# tractor_v2.net
KiCad netlist of a schematic drawn in EAGLE
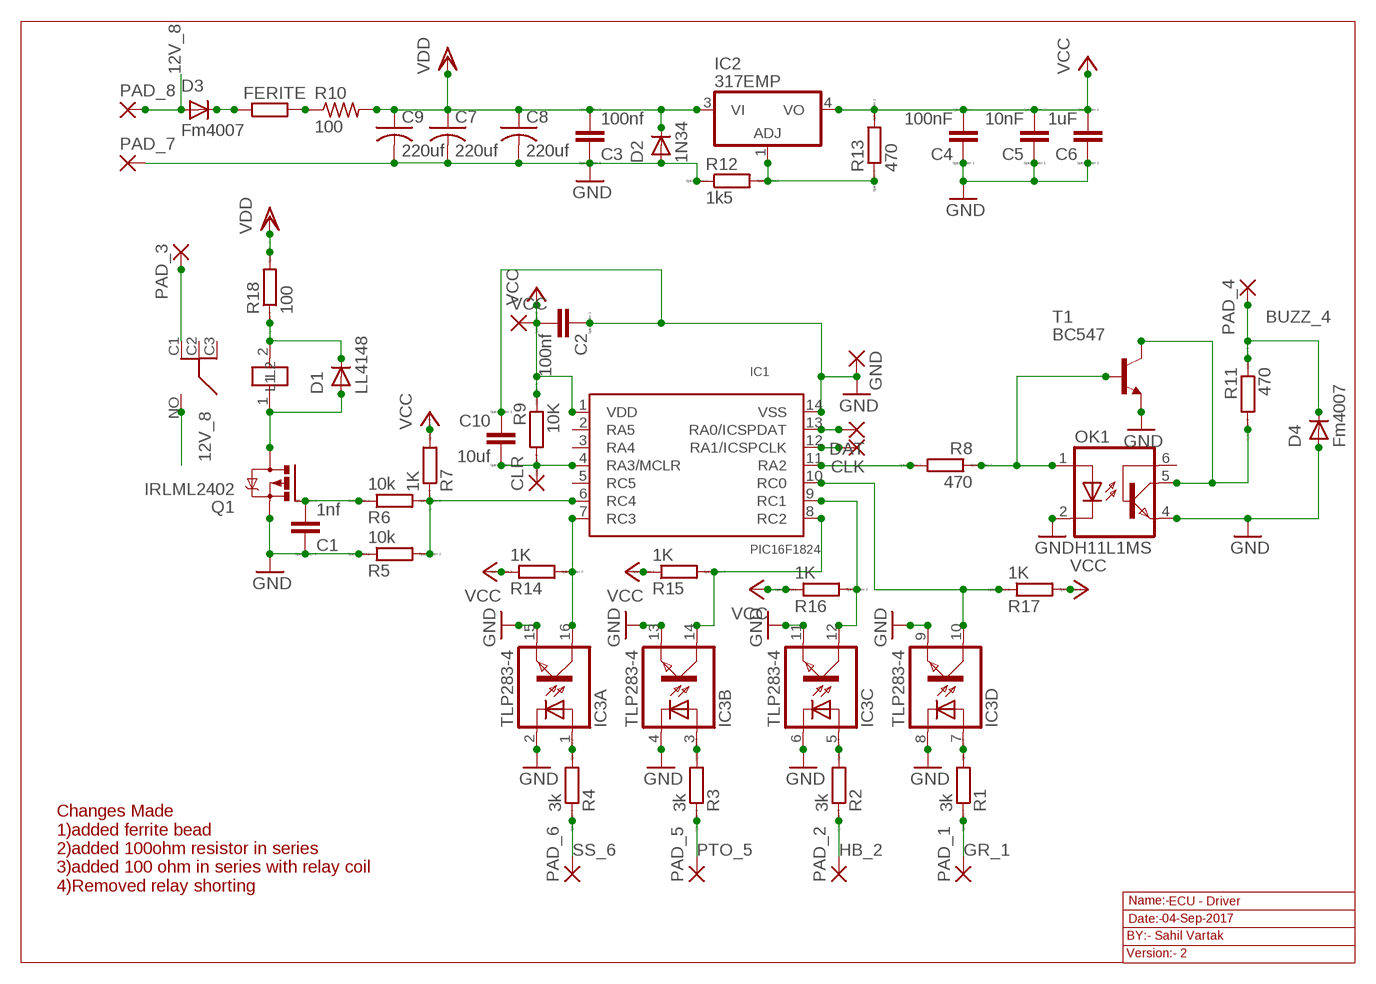
[diagram p0: schematic, sheet 1]

(export (version "E")
  (design (tool "Eeschema 10.0.6"))
  (components
    (comp (ref "C1")
      (value "1nf")
      (footprint "eagle-import:C0603")
      (libsource (lib "eagle-import") (part "CC0603"))
    )
    (comp (ref "C2")
      (value "100nf")
      (footprint "eagle-import:C0603")
      (libsource (lib "eagle-import") (part "CC0603"))
    )
    (comp (ref "C3")
      (value "100nf")
      (footprint "eagle-import:C0603")
      (libsource (lib "eagle-import") (part "CC0603"))
    )
    (comp (ref "C4")
      (value "100nF")
      (footprint "eagle-import:C0603")
      (libsource (lib "eagle-import") (part "CC0603"))
    )
    (comp (ref "C5")
      (value "10nF")
      (footprint "eagle-import:C0603")
      (libsource (lib "eagle-import") (part "CC0603"))
    )
    (comp (ref "C6")
      (value "1uF")
      (footprint "eagle-import:C0603")
      (libsource (lib "eagle-import") (part "CC0603"))
    )
    (comp (ref "C7")
      (value "220uf")
      (footprint "eagle-import:C025-025X050")
      (libsource (lib "eagle-import") (part "C-US025-025X050"))
    )
    (comp (ref "C8")
      (value "220uf")
      (footprint "eagle-import:C025-025X050")
      (libsource (lib "eagle-import") (part "C-US025-025X050"))
    )
    (comp (ref "C9")
      (value "220uf")
      (footprint "eagle-import:C025-025X050")
      (libsource (lib "eagle-import") (part "C-US025-025X050"))
    )
    (comp (ref "C10")
      (value "10uf")
      (footprint "eagle-import:C0603")
      (libsource (lib "eagle-import") (part "CC0603"))
    )
    (comp (ref "CLK")
      (value "1,6/0,8")
      (footprint "eagle-import:1,6_0,8")
      (libsource (lib "eagle-import") (part "1,6/0,8"))
    )
    (comp (ref "CLR")
      (value "1,6/0,8")
      (footprint "eagle-import:1,6_0,8")
      (libsource (lib "eagle-import") (part "1,6/0,8"))
    )
    (comp (ref "D1")
      (value "LL4148")
      (footprint "eagle-import:SMA-DO214AC")
      (libsource (lib "eagle-import") (part "GF1"))
    )
    (comp (ref "D2")
      (value "1N34")
      (footprint "eagle-import:SMA-DO214AC")
      (libsource (lib "eagle-import") (part "GF1"))
    )
    (comp (ref "D3")
      (value "Fm4007")
      (footprint "eagle-import:SMA-DO214AC")
      (libsource (lib "eagle-import") (part "GF1"))
    )
    (comp (ref "D4")
      (value "Fm4007")
      (footprint "eagle-import:SMA-DO214AC")
      (libsource (lib "eagle-import") (part "GF1"))
    )
    (comp (ref "DAT")
      (value "1,6/0,8")
      (footprint "eagle-import:1,6_0,8")
      (libsource (lib "eagle-import") (part "1,6/0,8"))
    )
    (comp (ref "FERITE")
      (value "R-EU_R0603")
      (footprint "eagle-import:R0603")
      (libsource (lib "eagle-import") (part "R-EU_R0603"))
    )
    (comp (ref "GND")
      (value "1,6/0,8")
      (footprint "eagle-import:1,6_0,8")
      (libsource (lib "eagle-import") (part "1,6/0,8"))
    )
    (comp (ref "IC1")
      (value "PIC16F1824")
      (footprint "eagle-import:SO-14")
      (libsource (lib "eagle-import") (part "PIC16F1824"))
    )
    (comp (ref "IC2")
      (value "317EMP")
      (footprint "eagle-import:SOT223")
      (libsource (lib "eagle-import") (part "317EMP"))
    )
    (comp (ref "IC3")
      (value "TLP283-4")
      (footprint "eagle-import:MINI-FLAT-16")
      (libsource (lib "eagle-import") (part "TLP283-4"))
    )
    (comp (ref "K2")
      (value "RL703")
      (footprint "eagle-import:RL703")
      (libsource (lib "eagle-import") (part "RL703"))
    )
    (comp (ref "OK1")
      (value "H11L1MS")
      (footprint "eagle-import:DIL6-SMD")
      (libsource (lib "eagle-import") (part "H11LMS1"))
    )
    (comp (ref "PAD_1")
      (value "2,54/1,1")
      (footprint "eagle-import:2,54_1,1")
      (libsource (lib "eagle-import") (part "2,54/1,1"))
    )
    (comp (ref "PAD_2")
      (value "2,54/1,1")
      (footprint "eagle-import:2,54_1,1")
      (libsource (lib "eagle-import") (part "2,54/1,1"))
    )
    (comp (ref "PAD_3")
      (value "2,54/1,1")
      (footprint "eagle-import:2,54_1,1")
      (libsource (lib "eagle-import") (part "2,54/1,1"))
    )
    (comp (ref "PAD_4")
      (value "2,54/1,1")
      (footprint "eagle-import:2,54_1,1")
      (libsource (lib "eagle-import") (part "2,54/1,1"))
    )
    (comp (ref "PAD_5")
      (value "2,54/1,1")
      (footprint "eagle-import:2,54_1,1")
      (libsource (lib "eagle-import") (part "2,54/1,1"))
    )
    (comp (ref "PAD_6")
      (value "2,54/1,1")
      (footprint "eagle-import:2,54_1,1")
      (libsource (lib "eagle-import") (part "2,54/1,1"))
    )
    (comp (ref "PAD_7")
      (value "2,54/1,1")
      (footprint "eagle-import:2,54_1,1")
      (libsource (lib "eagle-import") (part "2,54/1,1"))
    )
    (comp (ref "PAD_8")
      (value "2,54/1,1")
      (footprint "eagle-import:2,54_1,1")
      (libsource (lib "eagle-import") (part "2,54/1,1"))
    )
    (comp (ref "Q1")
      (value "IRLML2402")
      (footprint "eagle-import:MICRO3")
      (libsource (lib "eagle-import") (part "IRLML5203"))
    )
    (comp (ref "R1")
      (value "3k")
      (footprint "eagle-import:R0603")
      (libsource (lib "eagle-import") (part "RR0603"))
    )
    (comp (ref "R2")
      (value "3k")
      (footprint "eagle-import:R0603")
      (libsource (lib "eagle-import") (part "RR0603"))
    )
    (comp (ref "R3")
      (value "3k")
      (footprint "eagle-import:R0603")
      (libsource (lib "eagle-import") (part "RR0603"))
    )
    (comp (ref "R4")
      (value "3k")
      (footprint "eagle-import:R0603")
      (libsource (lib "eagle-import") (part "RR0603"))
    )
    (comp (ref "R5")
      (value "10k")
      (footprint "eagle-import:R0603")
      (libsource (lib "eagle-import") (part "RR0603"))
    )
    (comp (ref "R6")
      (value "10k")
      (footprint "eagle-import:R0603")
      (libsource (lib "eagle-import") (part "RR0603"))
    )
    (comp (ref "R7")
      (value "1K")
      (footprint "eagle-import:R0603")
      (libsource (lib "eagle-import") (part "RR0603"))
    )
    (comp (ref "R8")
      (value "470")
      (footprint "eagle-import:R0603")
      (libsource (lib "eagle-import") (part "RR0603"))
    )
    (comp (ref "R9")
      (value "10K")
      (footprint "eagle-import:R0603")
      (libsource (lib "eagle-import") (part "RR0603"))
    )
    (comp (ref "R10")
      (value "100")
      (footprint "eagle-import:WSC2515")
      (libsource (lib "eagle-import") (part "R-US_WSC2515"))
    )
    (comp (ref "R11")
      (value "470")
      (footprint "eagle-import:R0603")
      (libsource (lib "eagle-import") (part "RR0603"))
    )
    (comp (ref "R12")
      (value "1k5")
      (footprint "eagle-import:R0603")
      (libsource (lib "eagle-import") (part "RR0603"))
    )
    (comp (ref "R13")
      (value "470")
      (footprint "eagle-import:R0603")
      (libsource (lib "eagle-import") (part "RR0603"))
    )
    (comp (ref "R14")
      (value "1K")
      (footprint "eagle-import:R0603")
      (libsource (lib "eagle-import") (part "RR0603"))
    )
    (comp (ref "R15")
      (value "1K")
      (footprint "eagle-import:R0603")
      (libsource (lib "eagle-import") (part "RR0603"))
    )
    (comp (ref "R16")
      (value "1K")
      (footprint "eagle-import:R0603")
      (libsource (lib "eagle-import") (part "RR0603"))
    )
    (comp (ref "R17")
      (value "1K")
      (footprint "eagle-import:R0603")
      (libsource (lib "eagle-import") (part "RR0603"))
    )
    (comp (ref "R18")
      (value "100")
      (footprint "eagle-import:R0603")
      (libsource (lib "eagle-import") (part "RR0603"))
    )
    (comp (ref "T1")
      (value "BC547")
      (footprint "eagle-import:TO92")
      (libsource (lib "eagle-import") (part "BC547"))
    )
    (comp (ref "VCC")
      (value "1,6/0,8")
      (footprint "eagle-import:1,6_0,8")
      (libsource (lib "eagle-import") (part "1,6/0,8"))
    )
  )
  (nets
    (net (code "1") (name "/12V_8") (class "Default")
      (node (ref "D3") (pin "A") (pinfunction "A_A") (pintype "passive"))
      (node (ref "K2") (pin "NO") (pinfunction "NO_NO") (pintype "bidirectional"))
      (node (ref "PAD_8") (pin "1") (pinfunction "P_1") (pintype "passive"))
    )
    (net (code "2") (name "/BUZZ_4") (class "Default")
      (node (ref "D4") (pin "K") (pinfunction "C_K") (pintype "passive"))
      (node (ref "PAD_4") (pin "1") (pinfunction "P_1") (pintype "passive"))
      (node (ref "R11") (pin "1") (pinfunction "1_1") (pintype "passive"))
    )
    (net (code "3") (name "/GR_1") (class "Default")
      (node (ref "PAD_1") (pin "1") (pinfunction "P_1") (pintype "passive"))
      (node (ref "R1") (pin "1") (pinfunction "1_1") (pintype "passive"))
    )
    (net (code "4") (name "/HB_2") (class "Default")
      (node (ref "PAD_2") (pin "1") (pinfunction "P_1") (pintype "passive"))
      (node (ref "R2") (pin "1") (pinfunction "1_1") (pintype "passive"))
    )
    (net (code "5") (name "/PTO_5") (class "Default")
      (node (ref "PAD_5") (pin "1") (pinfunction "P_1") (pintype "passive"))
      (node (ref "R3") (pin "1") (pinfunction "1_1") (pintype "passive"))
    )
    (net (code "6") (name "/SS_6") (class "Default")
      (node (ref "PAD_6") (pin "1") (pinfunction "P_1") (pintype "passive"))
      (node (ref "R4") (pin "1") (pinfunction "1_1") (pintype "passive"))
    )
    (net (code "7") (name "GND") (class "Default")
      (node (ref "C1") (pin "1") (pinfunction "1_1") (pintype "passive"))
      (node (ref "C10") (pin "1") (pinfunction "1_1") (pintype "passive"))
      (node (ref "C2") (pin "1") (pinfunction "1_1") (pintype "passive"))
      (node (ref "C3") (pin "1") (pinfunction "1_1") (pintype "passive"))
      (node (ref "C4") (pin "1") (pinfunction "1_1") (pintype "passive"))
      (node (ref "C5") (pin "1") (pinfunction "1_1") (pintype "passive"))
      (node (ref "C6") (pin "1") (pinfunction "1_1") (pintype "passive"))
      (node (ref "C7") (pin "2") (pinfunction "2_2") (pintype "passive"))
      (node (ref "C8") (pin "2") (pinfunction "2_2") (pintype "passive"))
      (node (ref "C9") (pin "2") (pinfunction "2_2") (pintype "passive"))
      (node (ref "D2") (pin "A") (pinfunction "A_A") (pintype "passive"))
      (node (ref "D4") (pin "A") (pinfunction "A_A") (pintype "passive"))
      (node (ref "GND") (pin "1") (pinfunction "P_1") (pintype "passive"))
      (node (ref "IC1") (pin "14") (pinfunction "VSS_14") (pintype "bidirectional"))
      (node (ref "IC3") (pin "11") (pinfunction "EMIT_11") (pintype "passive"))
      (node (ref "IC3") (pin "13") (pinfunction "EMIT_13") (pintype "passive"))
      (node (ref "IC3") (pin "15") (pinfunction "EMIT_15") (pintype "passive"))
      (node (ref "IC3") (pin "2") (pinfunction "C_2") (pintype "passive"))
      (node (ref "IC3") (pin "4") (pinfunction "C_4") (pintype "passive"))
      (node (ref "IC3") (pin "6") (pinfunction "C_6") (pintype "passive"))
      (node (ref "IC3") (pin "8") (pinfunction "C_8") (pintype "passive"))
      (node (ref "IC3") (pin "9") (pinfunction "EMIT_9") (pintype "passive"))
      (node (ref "OK1") (pin "2") (pinfunction "C_2") (pintype "passive"))
      (node (ref "OK1") (pin "4") (pinfunction "EMI_4") (pintype "passive"))
      (node (ref "PAD_7") (pin "1") (pinfunction "P_1") (pintype "passive"))
      (node (ref "Q1") (pin "2") (pinfunction "S_2") (pintype "passive"))
      (node (ref "R12") (pin "1") (pinfunction "1_1") (pintype "passive"))
      (node (ref "R5") (pin "1") (pinfunction "1_1") (pintype "passive"))
      (node (ref "T1") (pin "1") (pinfunction "E_1") (pintype "passive"))
    )
    (net (code "8") (name "Net-(CLK-P)") (class "Default")
      (node (ref "CLK") (pin "1") (pinfunction "P_1") (pintype "passive"))
      (node (ref "IC1") (pin "12") (pinfunction "RA1/ICSPCLK_12") (pintype "bidirectional"))
    )
    (net (code "9") (name "Net-(CLR-P)") (class "Default")
      (node (ref "C10") (pin "2") (pinfunction "2_2") (pintype "passive"))
      (node (ref "CLR") (pin "1") (pinfunction "P_1") (pintype "passive"))
      (node (ref "IC1") (pin "4") (pinfunction "RA3/MCLR_4") (pintype "bidirectional"))
      (node (ref "R9") (pin "2") (pinfunction "2_2") (pintype "passive"))
    )
    (net (code "10") (name "Net-(D1-C)") (class "Default")
      (node (ref "D1") (pin "K") (pinfunction "C_K") (pintype "passive"))
      (node (ref "K2") (pin "2") (pinfunction "L1_2") (pintype "bidirectional"))
      (node (ref "R18") (pin "1") (pinfunction "1_1") (pintype "passive"))
    )
    (net (code "11") (name "Net-(D3-C)") (class "Default")
      (node (ref "D3") (pin "K") (pinfunction "C_K") (pintype "passive"))
      (node (ref "FERITE") (pin "1") (pinfunction "1_1") (pintype "passive"))
    )
    (net (code "12") (name "Net-(DAT-P)") (class "Default")
      (node (ref "DAT") (pin "1") (pinfunction "P_1") (pintype "passive"))
      (node (ref "IC1") (pin "13") (pinfunction "RA0/ICSPDAT_13") (pintype "bidirectional"))
    )
    (net (code "13") (name "Net-(FERITE-Pad2)") (class "Default")
      (node (ref "FERITE") (pin "2") (pinfunction "2_2") (pintype "passive"))
      (node (ref "R10") (pin "1") (pinfunction "1_1") (pintype "passive"))
    )
    (net (code "14") (name "Net-(IC1-RA2)") (class "Default")
      (node (ref "IC1") (pin "11") (pinfunction "RA2_11") (pintype "bidirectional"))
      (node (ref "R8") (pin "2") (pinfunction "2_2") (pintype "passive"))
    )
    (net (code "15") (name "Net-(IC1-RC0)") (class "Default")
      (node (ref "IC1") (pin "10") (pinfunction "RC0_10") (pintype "bidirectional"))
      (node (ref "IC3") (pin "10") (pinfunction "COL_10") (pintype "passive"))
      (node (ref "R17") (pin "1") (pinfunction "1_1") (pintype "passive"))
    )
    (net (code "16") (name "Net-(IC1-RC1)") (class "Default")
      (node (ref "IC1") (pin "9") (pinfunction "RC1_9") (pintype "bidirectional"))
      (node (ref "IC3") (pin "12") (pinfunction "COL_12") (pintype "passive"))
      (node (ref "R16") (pin "2") (pinfunction "2_2") (pintype "passive"))
    )
    (net (code "17") (name "Net-(IC1-RC2)") (class "Default")
      (node (ref "IC1") (pin "8") (pinfunction "RC2_8") (pintype "bidirectional"))
      (node (ref "IC3") (pin "14") (pinfunction "COL_14") (pintype "passive"))
      (node (ref "R15") (pin "2") (pinfunction "2_2") (pintype "passive"))
    )
    (net (code "18") (name "Net-(IC1-RC3)") (class "Default")
      (node (ref "IC1") (pin "7") (pinfunction "RC3_7") (pintype "bidirectional"))
      (node (ref "IC3") (pin "16") (pinfunction "COL_16") (pintype "passive"))
      (node (ref "R14") (pin "2") (pinfunction "2_2") (pintype "passive"))
    )
    (net (code "19") (name "Net-(IC1-RC4)") (class "Default")
      (node (ref "IC1") (pin "6") (pinfunction "RC4_6") (pintype "bidirectional"))
      (node (ref "R5") (pin "2") (pinfunction "2_2") (pintype "passive"))
      (node (ref "R6") (pin "2") (pinfunction "2_2") (pintype "passive"))
      (node (ref "R7") (pin "1") (pinfunction "1_1") (pintype "passive"))
    )
    (net (code "20") (name "Net-(IC2-ADJ)") (class "Default")
      (node (ref "IC2") (pin "1") (pinfunction "ADJ_1") (pintype "input"))
      (node (ref "R12") (pin "2") (pinfunction "2_2") (pintype "passive"))
      (node (ref "R13") (pin "1") (pinfunction "1_1") (pintype "passive"))
    )
    (net (code "21") (name "Net-(IC3A-A)") (class "Default")
      (node (ref "IC3") (pin "1") (pinfunction "A_1") (pintype "passive"))
      (node (ref "R4") (pin "2") (pinfunction "2_2") (pintype "passive"))
    )
    (net (code "22") (name "Net-(IC3B-A)") (class "Default")
      (node (ref "IC3") (pin "3") (pinfunction "A_3") (pintype "passive"))
      (node (ref "R3") (pin "2") (pinfunction "2_2") (pintype "passive"))
    )
    (net (code "23") (name "Net-(IC3C-A)") (class "Default")
      (node (ref "IC3") (pin "5") (pinfunction "A_5") (pintype "passive"))
      (node (ref "R2") (pin "2") (pinfunction "2_2") (pintype "passive"))
    )
    (net (code "24") (name "Net-(IC3D-A)") (class "Default")
      (node (ref "IC3") (pin "7") (pinfunction "A_7") (pintype "passive"))
      (node (ref "R1") (pin "2") (pinfunction "2_2") (pintype "passive"))
    )
    (net (code "25") (name "Net-(K2-L2)") (class "Default")
      (node (ref "D1") (pin "A") (pinfunction "A_A") (pintype "passive"))
      (node (ref "K2") (pin "1") (pinfunction "L2_1") (pintype "bidirectional"))
      (node (ref "Q1") (pin "3") (pinfunction "D_3") (pintype "passive"))
    )
    (net (code "26") (name "Net-(OK1-A)") (class "Default")
      (node (ref "OK1") (pin "1") (pinfunction "A_1") (pintype "passive"))
      (node (ref "R8") (pin "1") (pinfunction "1_1") (pintype "passive"))
      (node (ref "T1") (pin "2") (pinfunction "B_2") (pintype "passive"))
    )
    (net (code "27") (name "Net-(OK1-COL)") (class "Default")
      (node (ref "OK1") (pin "5") (pinfunction "COL_5") (pintype "passive"))
      (node (ref "R11") (pin "2") (pinfunction "2_2") (pintype "passive"))
      (node (ref "T1") (pin "3") (pinfunction "C_3") (pintype "passive"))
    )
    (net (code "28") (name "Net-(PAD_3-P)") (class "Default")
      (node (ref "K2") (pin "C1") (pinfunction "C1_C1") (pintype "bidirectional"))
      (node (ref "PAD_3") (pin "1") (pinfunction "P_1") (pintype "passive"))
    )
    (net (code "29") (name "Net-(Q1-G)") (class "Default")
      (node (ref "C1") (pin "2") (pinfunction "2_2") (pintype "passive"))
      (node (ref "Q1") (pin "1") (pinfunction "G_1") (pintype "passive"))
      (node (ref "R6") (pin "1") (pinfunction "1_1") (pintype "passive"))
    )
    (net (code "30") (name "VCC") (class "Default")
      (node (ref "C2") (pin "2") (pinfunction "2_2") (pintype "passive"))
      (node (ref "C4") (pin "2") (pinfunction "2_2") (pintype "passive"))
      (node (ref "C5") (pin "2") (pinfunction "2_2") (pintype "passive"))
      (node (ref "C6") (pin "2") (pinfunction "2_2") (pintype "passive"))
      (node (ref "IC1") (pin "1") (pinfunction "VDD_1") (pintype "bidirectional"))
      (node (ref "IC2") (pin "4") (pinfunction "VO_4") (pintype "passive"))
      (node (ref "R13") (pin "2") (pinfunction "2_2") (pintype "passive"))
      (node (ref "R14") (pin "1") (pinfunction "1_1") (pintype "passive"))
      (node (ref "R15") (pin "1") (pinfunction "1_1") (pintype "passive"))
      (node (ref "R16") (pin "1") (pinfunction "1_1") (pintype "passive"))
      (node (ref "R17") (pin "2") (pinfunction "2_2") (pintype "passive"))
      (node (ref "R7") (pin "2") (pinfunction "2_2") (pintype "passive"))
      (node (ref "R9") (pin "1") (pinfunction "1_1") (pintype "passive"))
      (node (ref "VCC") (pin "1") (pinfunction "P_1") (pintype "passive"))
    )
    (net (code "31") (name "VDD") (class "Default")
      (node (ref "C3") (pin "2") (pinfunction "2_2") (pintype "passive"))
      (node (ref "C7") (pin "1") (pinfunction "1_1") (pintype "passive"))
      (node (ref "C8") (pin "1") (pinfunction "1_1") (pintype "passive"))
      (node (ref "C9") (pin "1") (pinfunction "1_1") (pintype "passive"))
      (node (ref "D2") (pin "K") (pinfunction "C_K") (pintype "passive"))
      (node (ref "IC2") (pin "3") (pinfunction "VI_3") (pintype "input"))
      (node (ref "R10") (pin "2") (pinfunction "2_2") (pintype "passive"))
      (node (ref "R18") (pin "2") (pinfunction "2_2") (pintype "passive"))
    )
    (net (code "32") (name "unconnected-(IC1-RA4-Pad3)") (class "Default")
      (node (ref "IC1") (pin "3") (pinfunction "RA4_3") (pintype "bidirectional"))
    )
    (net (code "33") (name "unconnected-(IC1-RA5-Pad2)") (class "Default")
      (node (ref "IC1") (pin "2") (pinfunction "RA5_2") (pintype "bidirectional"))
    )
    (net (code "34") (name "unconnected-(IC1-RC5-Pad5)") (class "Default")
      (node (ref "IC1") (pin "5") (pinfunction "RC5_5") (pintype "bidirectional"))
    )
    (net (code "35") (name "unconnected-(K2-PadC2)") (class "Default")
      (node (ref "K2") (pin "C2") (pinfunction "C2_C2") (pintype "bidirectional"))
    )
    (net (code "36") (name "unconnected-(K2-PadC3)") (class "Default")
      (node (ref "K2") (pin "C3") (pinfunction "C3_C3") (pintype "bidirectional"))
    )
    (net (code "37") (name "unconnected-(OK1-BAS-Pad6)") (class "Default")
      (node (ref "OK1") (pin "6") (pinfunction "BAS_6") (pintype "passive"))
    )
  )
)
